# EnvNode.net
KiCad netlist of a schematic drawn in Altium Designer
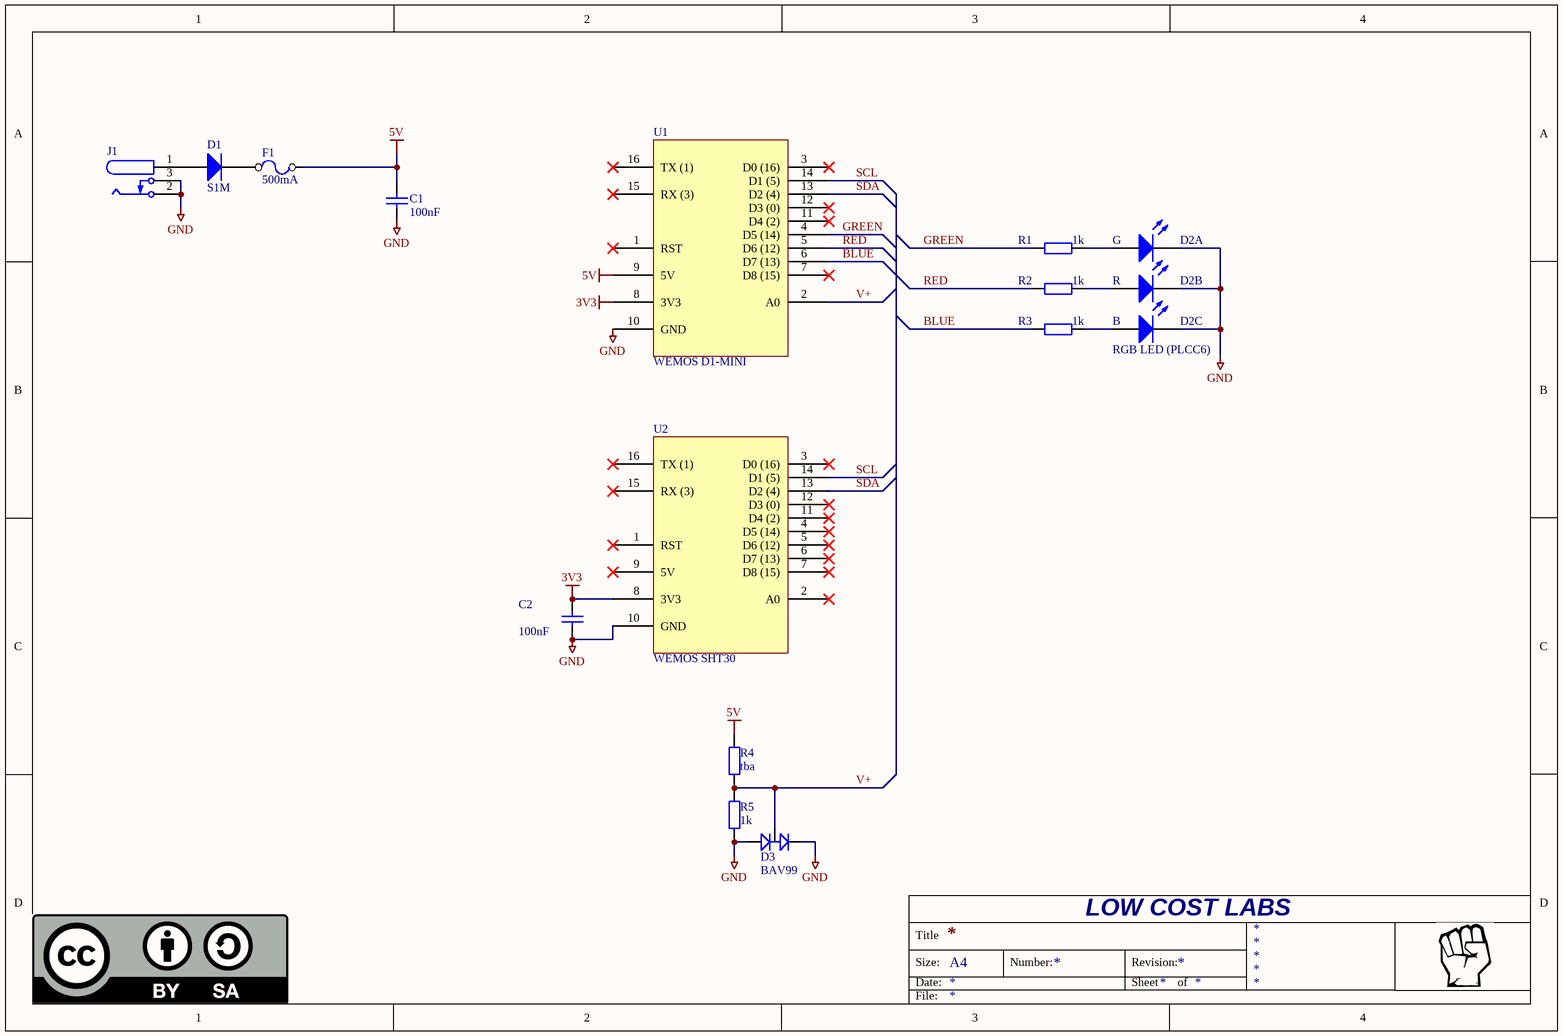
[diagram p0: EnvNode.SchDoc]

(export (version "E")
  (design (tool "Eeschema 10.0.6"))
  (components
    (comp (ref "C1")
      (value "100nF")
      (footprint "HAL9100:CAPACITOR 0805")
      (description "Capacitor")
      (fields (field (name "PUBLISHER") "Altium Limited"))
      (libsource (lib "Miscellaneous Devices") (part "Cap"))
    )
    (comp (ref "C2")
      (value "100nF")
      (footprint "HAL9100:CAPACITOR 0805")
      (description "Capacitor")
      (fields (field (name "PUBLISHER") "Altium Limited"))
      (libsource (lib "Miscellaneous Devices") (part "Cap"))
    )
    (comp (ref "D1")
      (value "S1M")
      (footprint "SMA")
      (description "DIODE S1M")
      (libsource (lib "HAL9100") (part "DIODE S1M (SMA)"))
    )
    (comp (ref "D2")
      (value "RGB LED (PLCC6)")
      (footprint "PLCC-6")
      (fields
        (field (name "MOUSER PART NO.") "604-WP132XIT")
        (field (name "FARNELL PART NO.") "1003393")
        (field (name "MANUFACTURER") "Kingbright")
      )
      (libsource (lib "NASCO") (part "RGB LED (PLCC6)"))
    )
    (comp (ref "D3")
      (value "BAV99")
      (footprint "SOT23-3L")
      (description "DUAL DIODE, BAV99")
      (fields (field (name "MOUSER PART NO.") "771-BAV99/T3") (field (name "FARNELL PART NO.") "9843612"))
      (libsource (lib "NASCO") (part "BAV99"))
    )
    (comp (ref "F1")
      (value "500mA")
      (footprint "POLYSWITHC 1210")
      (description "PTC 12V POLYFUSE SMT 1210 500mA (1210L110/12WR)")
      (libsource (lib "HAL9100") (part "PTC 12V POLYFUSE SMT 1210 1.10A"))
    )
    (comp (ref "J1")
      (value "Switchcraft RAPC722X")
      (footprint "25mm DC JACK")
      (description "Conn; AV; Power; Jack; Mini; 2.0mmPinDia; RtAngle; Thru-hole; forS760, S765Plug")
      (libsource (lib "HAL9100") (part "DC POWER JACK (3mm)"))
    )
    (comp (ref "R1")
      (value "1k")
      (footprint "HAL9100:RESISTOR 0805")
      (description "Resistor")
      (fields (field (name "PUBLISHER") "Altium Limited"))
      (libsource (lib "Miscellaneous Devices") (part "Res2"))
    )
    (comp (ref "R2")
      (value "1k")
      (footprint "HAL9100:RESISTOR 0805")
      (description "Resistor")
      (fields (field (name "PUBLISHER") "Altium Limited"))
      (libsource (lib "Miscellaneous Devices") (part "Res2"))
    )
    (comp (ref "R3")
      (value "1k")
      (footprint "HAL9100:RESISTOR 0805")
      (description "Resistor")
      (fields (field (name "PUBLISHER") "Altium Limited"))
      (libsource (lib "Miscellaneous Devices") (part "Res2"))
    )
    (comp (ref "R4")
      (value "tba")
      (footprint "HAL9100:RESISTOR 0805")
      (description "Resistor")
      (fields (field (name "PUBLISHER") "Altium Limited"))
      (libsource (lib "") (part "Res2_1"))
    )
    (comp (ref "R5")
      (value "1k")
      (footprint "HAL9100:RESISTOR 0805")
      (description "Resistor")
      (fields (field (name "PUBLISHER") "Altium Limited"))
      (libsource (lib "") (part "Res2_1"))
    )
    (comp (ref "U1")
      (value "WEMOS D1-MINI")
      (footprint "WEMOS PRO MINI")
      (libsource (lib "EnvNode") (part "WEMOS"))
    )
    (comp (ref "U2")
      (value "WEMOS SHT30")
      (footprint "WEMOS SHIELD")
      (libsource (lib "EnvNode") (part "WEMOS"))
    )
  )
  (nets
    (net (code "1") (name "/BLUE") (class "Default")
      (node (ref "R3") (pin "1") (pinfunction "1_1") (pintype "passive"))
      (node (ref "U1") (pin "6") (pinfunction "D7_(13)_6") (pintype "passive"))
    )
    (net (code "2") (name "/GREEN") (class "Default")
      (node (ref "R1") (pin "1") (pinfunction "1_1") (pintype "passive"))
      (node (ref "U1") (pin "4") (pinfunction "D5_(14)_4") (pintype "passive"))
    )
    (net (code "3") (name "/RED") (class "Default")
      (node (ref "R2") (pin "1") (pinfunction "1_1") (pintype "passive"))
      (node (ref "U1") (pin "5") (pinfunction "D6_(12)_5") (pintype "passive"))
    )
    (net (code "4") (name "/SCL") (class "Default")
      (node (ref "U1") (pin "14") (pinfunction "D1_(5)_14") (pintype "passive"))
      (node (ref "U2") (pin "14") (pinfunction "D1_(5)_14") (pintype "passive"))
    )
    (net (code "5") (name "/SDA") (class "Default")
      (node (ref "U1") (pin "13") (pinfunction "D2_(4)_13") (pintype "passive"))
      (node (ref "U2") (pin "13") (pinfunction "D2_(4)_13") (pintype "passive"))
    )
    (net (code "6") (name "/V+") (class "Default")
      (node (ref "D3") (pin "3") (pinfunction "C1/A2_3") (pintype "passive"))
      (node (ref "R4") (pin "1") (pinfunction "1_1") (pintype "passive"))
      (node (ref "R5") (pin "2") (pinfunction "2_2") (pintype "passive"))
      (node (ref "U1") (pin "2") (pinfunction "A0_2") (pintype "passive"))
    )
    (net (code "7") (name "3V3") (class "Default")
      (node (ref "C2") (pin "2") (pinfunction "2_2") (pintype "passive"))
      (node (ref "U1") (pin "8") (pinfunction "3V3_8") (pintype "passive"))
      (node (ref "U2") (pin "8") (pinfunction "3V3_8") (pintype "passive"))
    )
    (net (code "8") (name "5V") (class "Default")
      (node (ref "C1") (pin "2") (pinfunction "2_2") (pintype "passive"))
      (node (ref "F1") (pin "2") (pinfunction "2_2") (pintype "passive"))
      (node (ref "R4") (pin "2") (pinfunction "2_2") (pintype "passive"))
      (node (ref "U1") (pin "9") (pinfunction "5V_9") (pintype "passive"))
    )
    (net (code "9") (name "GND") (class "Default")
      (node (ref "C1") (pin "1") (pinfunction "1_1") (pintype "passive"))
      (node (ref "C2") (pin "1") (pinfunction "1_1") (pintype "passive"))
      (node (ref "D2") (pin "4") (pinfunction "K_4") (pintype "passive"))
      (node (ref "D2") (pin "5") (pinfunction "K_5") (pintype "passive"))
      (node (ref "D2") (pin "6") (pinfunction "K_6") (pintype "passive"))
      (node (ref "D3") (pin "1") (pinfunction "A1_1") (pintype "passive"))
      (node (ref "D3") (pin "2") (pinfunction "C2_2") (pintype "passive"))
      (node (ref "J1") (pin "2") (pinfunction "SLEEVE_2") (pintype "power_in"))
      (node (ref "J1") (pin "3") (pinfunction "SHUNT_3") (pintype "power_in"))
      (node (ref "R5") (pin "1") (pinfunction "1_1") (pintype "passive"))
      (node (ref "U1") (pin "10") (pinfunction "GND_10") (pintype "passive"))
      (node (ref "U2") (pin "10") (pinfunction "GND_10") (pintype "passive"))
    )
    (net (code "10") (name "Net-(D1-A)") (class "Default")
      (node (ref "D1") (pin "1") (pinfunction "A_1") (pintype "passive"))
      (node (ref "J1") (pin "1") (pinfunction "TIP_1") (pintype "power_in"))
    )
    (net (code "11") (name "Net-(D1-K)") (class "Default")
      (node (ref "D1") (pin "2") (pinfunction "K_2") (pintype "passive"))
      (node (ref "F1") (pin "1") (pinfunction "1_1") (pintype "passive"))
    )
    (net (code "12") (name "Net-(D2A-A)") (class "Default")
      (node (ref "D2") (pin "1") (pinfunction "A_1") (pintype "passive"))
      (node (ref "R1") (pin "2") (pinfunction "2_2") (pintype "passive"))
    )
    (net (code "13") (name "Net-(D2B-A)") (class "Default")
      (node (ref "D2") (pin "2") (pinfunction "A_2") (pintype "passive"))
      (node (ref "R2") (pin "2") (pinfunction "2_2") (pintype "passive"))
    )
    (net (code "14") (name "Net-(D2C-A)") (class "Default")
      (node (ref "D2") (pin "3") (pinfunction "A_3") (pintype "passive"))
      (node (ref "R3") (pin "2") (pinfunction "2_2") (pintype "passive"))
    )
    (net (code "15") (name "unconnected-(U1-D0_(16)-Pad3)") (class "Default")
      (node (ref "U1") (pin "3") (pinfunction "D0_(16)_3") (pintype "passive+no_connect"))
    )
    (net (code "16") (name "unconnected-(U1-D3_(0)-Pad12)") (class "Default")
      (node (ref "U1") (pin "12") (pinfunction "D3_(0)_12") (pintype "passive+no_connect"))
    )
    (net (code "17") (name "unconnected-(U1-D4_(2)-Pad11)") (class "Default")
      (node (ref "U1") (pin "11") (pinfunction "D4_(2)_11") (pintype "passive+no_connect"))
    )
    (net (code "18") (name "unconnected-(U1-D8_(15)-Pad7)") (class "Default")
      (node (ref "U1") (pin "7") (pinfunction "D8_(15)_7") (pintype "passive+no_connect"))
    )
    (net (code "19") (name "unconnected-(U1-RST-Pad1)") (class "Default")
      (node (ref "U1") (pin "1") (pinfunction "RST_1") (pintype "passive+no_connect"))
    )
    (net (code "20") (name "unconnected-(U1-RX_(3)-Pad15)") (class "Default")
      (node (ref "U1") (pin "15") (pinfunction "RX_(3)_15") (pintype "passive+no_connect"))
    )
    (net (code "21") (name "unconnected-(U1-TX_(1)-Pad16)") (class "Default")
      (node (ref "U1") (pin "16") (pinfunction "TX_(1)_16") (pintype "passive+no_connect"))
    )
    (net (code "22") (name "unconnected-(U2-5V-Pad9)") (class "Default")
      (node (ref "U2") (pin "9") (pinfunction "5V_9") (pintype "passive+no_connect"))
    )
    (net (code "23") (name "unconnected-(U2-A0-Pad2)") (class "Default")
      (node (ref "U2") (pin "2") (pinfunction "A0_2") (pintype "passive+no_connect"))
    )
    (net (code "24") (name "unconnected-(U2-D0_(16)-Pad3)") (class "Default")
      (node (ref "U2") (pin "3") (pinfunction "D0_(16)_3") (pintype "passive+no_connect"))
    )
    (net (code "25") (name "unconnected-(U2-D3_(0)-Pad12)") (class "Default")
      (node (ref "U2") (pin "12") (pinfunction "D3_(0)_12") (pintype "passive+no_connect"))
    )
    (net (code "26") (name "unconnected-(U2-D4_(2)-Pad11)") (class "Default")
      (node (ref "U2") (pin "11") (pinfunction "D4_(2)_11") (pintype "passive+no_connect"))
    )
    (net (code "27") (name "unconnected-(U2-D5_(14)-Pad4)") (class "Default")
      (node (ref "U2") (pin "4") (pinfunction "D5_(14)_4") (pintype "passive+no_connect"))
    )
    (net (code "28") (name "unconnected-(U2-D6_(12)-Pad5)") (class "Default")
      (node (ref "U2") (pin "5") (pinfunction "D6_(12)_5") (pintype "passive+no_connect"))
    )
    (net (code "29") (name "unconnected-(U2-D7_(13)-Pad6)") (class "Default")
      (node (ref "U2") (pin "6") (pinfunction "D7_(13)_6") (pintype "passive+no_connect"))
    )
    (net (code "30") (name "unconnected-(U2-D8_(15)-Pad7)") (class "Default")
      (node (ref "U2") (pin "7") (pinfunction "D8_(15)_7") (pintype "passive+no_connect"))
    )
    (net (code "31") (name "unconnected-(U2-RST-Pad1)") (class "Default")
      (node (ref "U2") (pin "1") (pinfunction "RST_1") (pintype "passive+no_connect"))
    )
    (net (code "32") (name "unconnected-(U2-RX_(3)-Pad15)") (class "Default")
      (node (ref "U2") (pin "15") (pinfunction "RX_(3)_15") (pintype "passive+no_connect"))
    )
    (net (code "33") (name "unconnected-(U2-TX_(1)-Pad16)") (class "Default")
      (node (ref "U2") (pin "16") (pinfunction "TX_(1)_16") (pintype "passive+no_connect"))
    )
  )
)
